# Irrigation_Controller.net
KiCad netlist of a schematic drawn in EAGLE
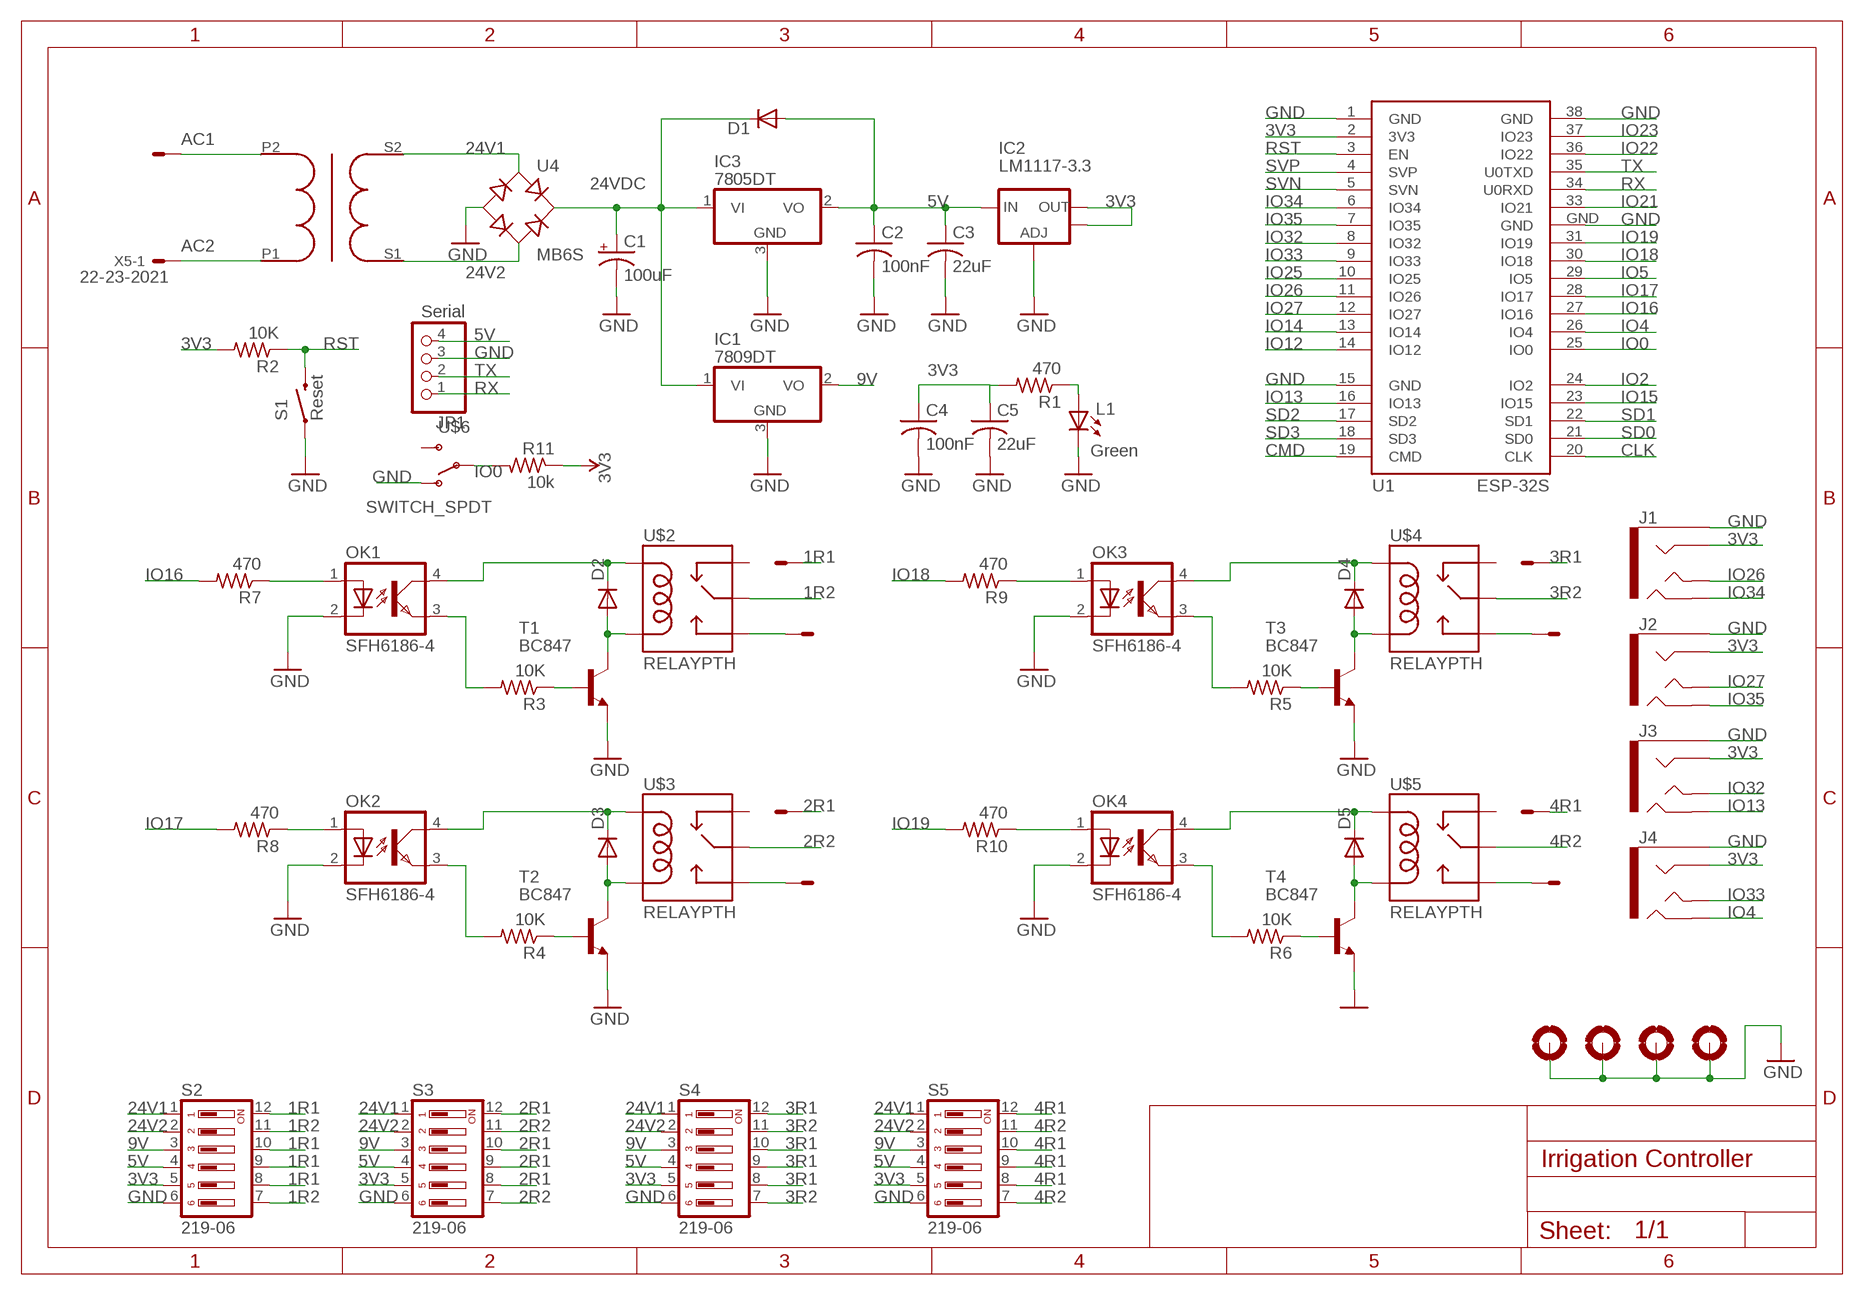
[diagram p0: schematic, sheet 1]

(export (version "E")
  (design (tool "Eeschema 10.0.6"))
  (components
    (comp (ref "C1")
      (value "100uF")
      (footprint "eagle-import:CT7343")
      (libsource (lib "eagle-import") (part "CPOL-USCT7343"))
    )
    (comp (ref "C2")
      (value "100nF")
      (footprint "eagle-import:1206")
      (libsource (lib "eagle-import") (part "C1206"))
    )
    (comp (ref "C3")
      (value "22uF")
      (footprint "eagle-import:1206")
      (libsource (lib "eagle-import") (part "C1206"))
    )
    (comp (ref "C4")
      (value "100nF")
      (footprint "eagle-import:1206")
      (libsource (lib "eagle-import") (part "C1206"))
    )
    (comp (ref "C5")
      (value "22uF")
      (footprint "eagle-import:1206")
      (libsource (lib "eagle-import") (part "C1206"))
    )
    (comp (ref "D1")
      (value "DIODE-SOD123")
      (footprint "eagle-import:SOD123")
      (libsource (lib "eagle-import") (part "DIODE-SOD123"))
    )
    (comp (ref "D2")
      (value "DIODE-SOD123")
      (footprint "eagle-import:SOD123")
      (libsource (lib "eagle-import") (part "DIODE-SOD123"))
    )
    (comp (ref "D3")
      (value "DIODE-SOD123")
      (footprint "eagle-import:SOD123")
      (libsource (lib "eagle-import") (part "DIODE-SOD123"))
    )
    (comp (ref "D4")
      (value "DIODE-SOD123")
      (footprint "eagle-import:SOD123")
      (libsource (lib "eagle-import") (part "DIODE-SOD123"))
    )
    (comp (ref "D5")
      (value "DIODE-SOD123")
      (footprint "eagle-import:SOD123")
      (libsource (lib "eagle-import") (part "DIODE-SOD123"))
    )
    (comp (ref "H1")
      (value "MOUNT-PAD-ROUND3.0")
      (footprint "eagle-import:3,0-PAD")
      (libsource (lib "eagle-import") (part "MOUNT-PAD-ROUND3.0"))
    )
    (comp (ref "H2")
      (value "MOUNT-PAD-ROUND3.0")
      (footprint "eagle-import:3,0-PAD")
      (libsource (lib "eagle-import") (part "MOUNT-PAD-ROUND3.0"))
    )
    (comp (ref "H3")
      (value "MOUNT-PAD-ROUND3.0")
      (footprint "eagle-import:3,0-PAD")
      (libsource (lib "eagle-import") (part "MOUNT-PAD-ROUND3.0"))
    )
    (comp (ref "H4")
      (value "MOUNT-PAD-ROUND3.0")
      (footprint "eagle-import:3,0-PAD")
      (libsource (lib "eagle-import") (part "MOUNT-PAD-ROUND3.0"))
    )
    (comp (ref "IC1")
      (value "7809DT")
      (footprint "eagle-import:TO252")
      (libsource (lib "eagle-import") (part "78DT05"))
    )
    (comp (ref "IC2")
      (value "LM1117-3.3")
      (footprint "eagle-import:SOT223")
      (libsource (lib "eagle-import") (part "V_REG_LM1117SOT223"))
    )
    (comp (ref "IC3")
      (value "7805DT")
      (footprint "eagle-import:TO252")
      (libsource (lib "eagle-import") (part "78DT05"))
    )
    (comp (ref "J1")
      (value "AUDIO_JACK_TRRSSMD_RA")
      (footprint "eagle-import:AUDIO_JACK_3.5MM_TRRS_SMD_RA")
      (libsource (lib "eagle-import") (part "AUDIO_JACK_TRRSSMD_RA"))
    )
    (comp (ref "J2")
      (value "AUDIO_JACK_TRRSSMD_RA")
      (footprint "eagle-import:AUDIO_JACK_3.5MM_TRRS_SMD_RA")
      (libsource (lib "eagle-import") (part "AUDIO_JACK_TRRSSMD_RA"))
    )
    (comp (ref "J3")
      (value "AUDIO_JACK_TRRSSMD_RA")
      (footprint "eagle-import:AUDIO_JACK_3.5MM_TRRS_SMD_RA")
      (libsource (lib "eagle-import") (part "AUDIO_JACK_TRRSSMD_RA"))
    )
    (comp (ref "J4")
      (value "AUDIO_JACK_TRRSSMD_RA")
      (footprint "eagle-import:AUDIO_JACK_3.5MM_TRRS_SMD_RA")
      (libsource (lib "eagle-import") (part "AUDIO_JACK_TRRSSMD_RA"))
    )
    (comp (ref "JP1")
      (value "Serial")
      (footprint "eagle-import:1X04")
      (libsource (lib "eagle-import") (part "PINHD-1X4"))
    )
    (comp (ref "L1")
      (value "Green")
      (footprint "eagle-import:LED1206")
      (libsource (lib "eagle-import") (part "LED1206"))
    )
    (comp (ref "OK1")
      (value "SFH6186-4")
      (footprint "eagle-import:SMD4-7")
      (fields (field (name "MF") "VISHAY/TELEFUNKEN"))
      (libsource (lib "eagle-import") (part "SFH618?6-4"))
    )
    (comp (ref "OK2")
      (value "SFH6186-4")
      (footprint "eagle-import:SMD4-7")
      (fields (field (name "MF") "VISHAY/TELEFUNKEN"))
      (libsource (lib "eagle-import") (part "SFH618?6-4"))
    )
    (comp (ref "OK3")
      (value "SFH6186-4")
      (footprint "eagle-import:SMD4-7")
      (fields (field (name "MF") "VISHAY/TELEFUNKEN"))
      (libsource (lib "eagle-import") (part "SFH618?6-4"))
    )
    (comp (ref "OK4")
      (value "SFH6186-4")
      (footprint "eagle-import:SMD4-7")
      (fields (field (name "MF") "VISHAY/TELEFUNKEN"))
      (libsource (lib "eagle-import") (part "SFH618?6-4"))
    )
    (comp (ref "R1")
      (value "470")
      (footprint "eagle-import:1206")
      (libsource (lib "eagle-import") (part "R1206"))
    )
    (comp (ref "R2")
      (value "10K")
      (footprint "eagle-import:R1206")
      (libsource (lib "eagle-import") (part "R-US_R1206"))
    )
    (comp (ref "R3")
      (value "10K")
      (footprint "eagle-import:R1206")
      (libsource (lib "eagle-import") (part "R-US_R1206"))
    )
    (comp (ref "R4")
      (value "10K")
      (footprint "eagle-import:R1206")
      (libsource (lib "eagle-import") (part "R-US_R1206"))
    )
    (comp (ref "R5")
      (value "10K")
      (footprint "eagle-import:R1206")
      (libsource (lib "eagle-import") (part "R-US_R1206"))
    )
    (comp (ref "R6")
      (value "10K")
      (footprint "eagle-import:R1206")
      (libsource (lib "eagle-import") (part "R-US_R1206"))
    )
    (comp (ref "R7")
      (value "470")
      (footprint "eagle-import:R1206")
      (libsource (lib "eagle-import") (part "R-US_R1206"))
    )
    (comp (ref "R8")
      (value "470")
      (footprint "eagle-import:R1206")
      (libsource (lib "eagle-import") (part "R-US_R1206"))
    )
    (comp (ref "R9")
      (value "470")
      (footprint "eagle-import:R1206")
      (libsource (lib "eagle-import") (part "R-US_R1206"))
    )
    (comp (ref "R10")
      (value "470")
      (footprint "eagle-import:R1206")
      (libsource (lib "eagle-import") (part "R-US_R1206"))
    )
    (comp (ref "R11")
      (value "10k")
      (footprint "eagle-import:1206")
      (libsource (lib "eagle-import") (part "R1206"))
    )
    (comp (ref "S1")
      (value "Reset")
      (footprint "eagle-import:TACTILE_SWITCH_TALL")
      (libsource (lib "eagle-import") (part "SWITCH-MOMENTARY-2SMD-4"))
    )
    (comp (ref "S2")
      (value "219-06")
      (footprint "eagle-import:CTS-219-06")
      (libsource (lib "eagle-import") (part "219-06"))
    )
    (comp (ref "S3")
      (value "219-06")
      (footprint "eagle-import:CTS-219-06")
      (libsource (lib "eagle-import") (part "219-06"))
    )
    (comp (ref "S4")
      (value "219-06")
      (footprint "eagle-import:CTS-219-06")
      (libsource (lib "eagle-import") (part "219-06"))
    )
    (comp (ref "S5")
      (value "219-06")
      (footprint "eagle-import:CTS-219-06")
      (libsource (lib "eagle-import") (part "219-06"))
    )
    (comp (ref "T1")
      (value "BC847")
      (footprint "eagle-import:SOT23")
      (libsource (lib "eagle-import") (part "BC847"))
    )
    (comp (ref "T2")
      (value "BC847")
      (footprint "eagle-import:SOT23")
      (libsource (lib "eagle-import") (part "BC847"))
    )
    (comp (ref "T3")
      (value "BC847")
      (footprint "eagle-import:SOT23")
      (libsource (lib "eagle-import") (part "BC847"))
    )
    (comp (ref "T4")
      (value "BC847")
      (footprint "eagle-import:SOT23")
      (libsource (lib "eagle-import") (part "BC847"))
    )
    (comp (ref "U$1")
      (value "TRANSFORMADOR_PE3010-M")
      (footprint "eagle-import:TRANSFORMADOR_PE3010-M")
      (libsource (lib "eagle-import") (part "TRANSFORMADOR_PE3010-M"))
    )
    (comp (ref "U$2")
      (value "RELAYPTH")
      (footprint "eagle-import:SRD-05VDC-SL-C")
      (libsource (lib "eagle-import") (part "RELAYPTH"))
    )
    (comp (ref "U$3")
      (value "RELAYPTH")
      (footprint "eagle-import:SRD-05VDC-SL-C")
      (libsource (lib "eagle-import") (part "RELAYPTH"))
    )
    (comp (ref "U$4")
      (value "RELAYPTH")
      (footprint "eagle-import:SRD-05VDC-SL-C")
      (libsource (lib "eagle-import") (part "RELAYPTH"))
    )
    (comp (ref "U$5")
      (value "RELAYPTH")
      (footprint "eagle-import:SRD-05VDC-SL-C")
      (libsource (lib "eagle-import") (part "RELAYPTH"))
    )
    (comp (ref "U$6")
      (value "SWITCH_SPDT")
      (footprint "eagle-import:KPS-1290")
      (libsource (lib "eagle-import") (part "SWITCH_SPDT"))
    )
    (comp (ref "U1")
      (value "ESP-32S")
      (footprint "eagle-import:ESP-32S")
      (libsource (lib "eagle-import") (part "ESP-32S"))
    )
    (comp (ref "U4")
      (value "MB6S")
      (footprint "eagle-import:SOIC-4")
      (libsource (lib "eagle-import") (part "MBS6"))
    )
    (comp (ref "X1")
      (value "22-23-2021")
      (footprint "eagle-import:22-23-2021")
      (fields (field (name "MF") "MOLEX"))
      (libsource (lib "eagle-import") (part "22-23-2021"))
    )
    (comp (ref "X2")
      (value "22-23-2021")
      (footprint "eagle-import:22-23-2021")
      (fields (field (name "MF") "MOLEX"))
      (libsource (lib "eagle-import") (part "22-23-2021"))
    )
    (comp (ref "X3")
      (value "22-23-2021")
      (footprint "eagle-import:22-23-2021")
      (fields (field (name "MF") "MOLEX"))
      (libsource (lib "eagle-import") (part "22-23-2021"))
    )
    (comp (ref "X4")
      (value "22-23-2021")
      (footprint "eagle-import:22-23-2021")
      (fields (field (name "MF") "MOLEX"))
      (libsource (lib "eagle-import") (part "22-23-2021"))
    )
    (comp (ref "X5")
      (value "22-23-2021")
      (footprint "eagle-import:22-23-2021")
      (fields (field (name "MF") "MOLEX"))
      (libsource (lib "eagle-import") (part "22-23-2021"))
    )
  )
  (nets
    (net (code "1") (name "/1R1") (class "Default")
      (node (ref "S2") (pin "10") (pinfunction "10_10") (pintype "passive"))
      (node (ref "S2") (pin "12") (pinfunction "12_12") (pintype "passive"))
      (node (ref "S2") (pin "8") (pinfunction "8_8") (pintype "passive"))
      (node (ref "S2") (pin "9") (pinfunction "9_9") (pintype "passive"))
      (node (ref "X1") (pin "1") (pinfunction "S_1") (pintype "passive"))
    )
    (net (code "2") (name "/1R2") (class "Default")
      (node (ref "S2") (pin "11") (pinfunction "11_11") (pintype "passive"))
      (node (ref "S2") (pin "7") (pinfunction "7_7") (pintype "passive"))
      (node (ref "U$2") (pin "SWCOMMON") (pinfunction "SWCOMMON_SWCOMMON") (pintype "bidirectional"))
    )
    (net (code "3") (name "/2R1") (class "Default")
      (node (ref "S3") (pin "10") (pinfunction "10_10") (pintype "passive"))
      (node (ref "S3") (pin "12") (pinfunction "12_12") (pintype "passive"))
      (node (ref "S3") (pin "8") (pinfunction "8_8") (pintype "passive"))
      (node (ref "S3") (pin "9") (pinfunction "9_9") (pintype "passive"))
      (node (ref "X2") (pin "1") (pinfunction "S_1") (pintype "passive"))
    )
    (net (code "4") (name "/2R2") (class "Default")
      (node (ref "S3") (pin "11") (pinfunction "11_11") (pintype "passive"))
      (node (ref "S3") (pin "7") (pinfunction "7_7") (pintype "passive"))
      (node (ref "U$3") (pin "SWCOMMON") (pinfunction "SWCOMMON_SWCOMMON") (pintype "bidirectional"))
    )
    (net (code "5") (name "/3R1") (class "Default")
      (node (ref "S4") (pin "10") (pinfunction "10_10") (pintype "passive"))
      (node (ref "S4") (pin "12") (pinfunction "12_12") (pintype "passive"))
      (node (ref "S4") (pin "8") (pinfunction "8_8") (pintype "passive"))
      (node (ref "S4") (pin "9") (pinfunction "9_9") (pintype "passive"))
      (node (ref "X3") (pin "1") (pinfunction "S_1") (pintype "passive"))
    )
    (net (code "6") (name "/3R2") (class "Default")
      (node (ref "S4") (pin "11") (pinfunction "11_11") (pintype "passive"))
      (node (ref "S4") (pin "7") (pinfunction "7_7") (pintype "passive"))
      (node (ref "U$4") (pin "SWCOMMON") (pinfunction "SWCOMMON_SWCOMMON") (pintype "bidirectional"))
    )
    (net (code "7") (name "/4R1") (class "Default")
      (node (ref "S5") (pin "10") (pinfunction "10_10") (pintype "passive"))
      (node (ref "S5") (pin "12") (pinfunction "12_12") (pintype "passive"))
      (node (ref "S5") (pin "8") (pinfunction "8_8") (pintype "passive"))
      (node (ref "S5") (pin "9") (pinfunction "9_9") (pintype "passive"))
      (node (ref "X4") (pin "1") (pinfunction "S_1") (pintype "passive"))
    )
    (net (code "8") (name "/4R2") (class "Default")
      (node (ref "S5") (pin "11") (pinfunction "11_11") (pintype "passive"))
      (node (ref "S5") (pin "7") (pinfunction "7_7") (pintype "passive"))
      (node (ref "U$5") (pin "SWCOMMON") (pinfunction "SWCOMMON_SWCOMMON") (pintype "bidirectional"))
    )
    (net (code "9") (name "/5V") (class "Default")
      (node (ref "C2") (pin "1") (pinfunction "1_1") (pintype "passive"))
      (node (ref "C3") (pin "1") (pinfunction "1_1") (pintype "passive"))
      (node (ref "D1") (pin "A") (pinfunction "A_A") (pintype "passive"))
      (node (ref "IC2") (pin "3") (pinfunction "IN_3") (pintype "input"))
      (node (ref "IC3") (pin "2") (pinfunction "VO_2") (pintype "passive"))
      (node (ref "JP1") (pin "4") (pinfunction "4_4") (pintype "passive"))
      (node (ref "S2") (pin "4") (pinfunction "4_4") (pintype "passive"))
      (node (ref "S3") (pin "4") (pinfunction "4_4") (pintype "passive"))
      (node (ref "S4") (pin "4") (pinfunction "4_4") (pintype "passive"))
      (node (ref "S5") (pin "4") (pinfunction "4_4") (pintype "passive"))
    )
    (net (code "10") (name "/9V") (class "Default")
      (node (ref "IC1") (pin "2") (pinfunction "VO_2") (pintype "passive"))
      (node (ref "S2") (pin "3") (pinfunction "3_3") (pintype "passive"))
      (node (ref "S3") (pin "3") (pinfunction "3_3") (pintype "passive"))
      (node (ref "S4") (pin "3") (pinfunction "3_3") (pintype "passive"))
      (node (ref "S5") (pin "3") (pinfunction "3_3") (pintype "passive"))
    )
    (net (code "11") (name "/24V1") (class "Default")
      (node (ref "S2") (pin "1") (pinfunction "1_1") (pintype "passive"))
      (node (ref "S3") (pin "1") (pinfunction "1_1") (pintype "passive"))
      (node (ref "S4") (pin "1") (pinfunction "1_1") (pintype "passive"))
      (node (ref "S5") (pin "1") (pinfunction "1_1") (pintype "passive"))
      (node (ref "U$1") (pin "S2") (pinfunction "S2_S2") (pintype "bidirectional"))
      (node (ref "U4") (pin "~1") (pinfunction "AC1_~1") (pintype "passive"))
    )
    (net (code "12") (name "/24V2") (class "Default")
      (node (ref "S2") (pin "2") (pinfunction "2_2") (pintype "passive"))
      (node (ref "S3") (pin "2") (pinfunction "2_2") (pintype "passive"))
      (node (ref "S4") (pin "2") (pinfunction "2_2") (pintype "passive"))
      (node (ref "S5") (pin "2") (pinfunction "2_2") (pintype "passive"))
      (node (ref "U$1") (pin "S1") (pinfunction "S1_S1") (pintype "bidirectional"))
      (node (ref "U4") (pin "~2") (pinfunction "AC2_~2") (pintype "passive"))
    )
    (net (code "13") (name "/24VDC") (class "Default")
      (node (ref "C1") (pin "+") (pinfunction "+_+") (pintype "passive"))
      (node (ref "D1") (pin "C") (pinfunction "C_C") (pintype "passive"))
      (node (ref "IC1") (pin "1") (pinfunction "VI_1") (pintype "input"))
      (node (ref "IC3") (pin "1") (pinfunction "VI_1") (pintype "input"))
      (node (ref "U4") (pin "+") (pinfunction "+_+") (pintype "passive"))
    )
    (net (code "14") (name "/AC1") (class "Default")
      (node (ref "U$1") (pin "P2") (pinfunction "P2_P2") (pintype "bidirectional"))
      (node (ref "X5") (pin "2") (pinfunction "S_2") (pintype "passive"))
    )
    (net (code "15") (name "/AC2") (class "Default")
      (node (ref "U$1") (pin "P1") (pinfunction "P1_P1") (pintype "bidirectional"))
      (node (ref "X5") (pin "1") (pinfunction "S_1") (pintype "passive"))
    )
    (net (code "16") (name "/CLK") (class "Default")
      (node (ref "U1") (pin "20") (pinfunction "CLK_20") (pintype "bidirectional"))
    )
    (net (code "17") (name "/CMD") (class "Default")
      (node (ref "U1") (pin "19") (pinfunction "CMD_19") (pintype "bidirectional"))
    )
    (net (code "18") (name "/IO0") (class "Default")
      (node (ref "R11") (pin "2") (pinfunction "2_2") (pintype "passive"))
      (node (ref "U$6") (pin "P") (pinfunction "P_P") (pintype "passive"))
      (node (ref "U1") (pin "25") (pinfunction "IO0_25") (pintype "bidirectional"))
    )
    (net (code "19") (name "/IO2") (class "Default")
      (node (ref "U1") (pin "24") (pinfunction "IO2_24") (pintype "bidirectional"))
    )
    (net (code "20") (name "/IO4") (class "Default")
      (node (ref "J4") (pin "RING2") (pinfunction "RING2_RING2") (pintype "bidirectional"))
      (node (ref "U1") (pin "26") (pinfunction "IO4_26") (pintype "bidirectional"))
    )
    (net (code "21") (name "/IO5") (class "Default")
      (node (ref "U1") (pin "29") (pinfunction "IO5_29") (pintype "bidirectional"))
    )
    (net (code "22") (name "/IO12") (class "Default")
      (node (ref "U1") (pin "14") (pinfunction "IO12_14") (pintype "bidirectional"))
    )
    (net (code "23") (name "/IO13") (class "Default")
      (node (ref "J3") (pin "RING2") (pinfunction "RING2_RING2") (pintype "bidirectional"))
      (node (ref "U1") (pin "16") (pinfunction "IO13_16") (pintype "bidirectional"))
    )
    (net (code "24") (name "/IO14") (class "Default")
      (node (ref "U1") (pin "13") (pinfunction "IO14_13") (pintype "bidirectional"))
    )
    (net (code "25") (name "/IO15") (class "Default")
      (node (ref "U1") (pin "23") (pinfunction "IO15_23") (pintype "bidirectional"))
    )
    (net (code "26") (name "/IO16") (class "Default")
      (node (ref "R7") (pin "2") (pinfunction "2_2") (pintype "passive"))
      (node (ref "U1") (pin "27") (pinfunction "IO16_27") (pintype "bidirectional"))
    )
    (net (code "27") (name "/IO17") (class "Default")
      (node (ref "R8") (pin "2") (pinfunction "2_2") (pintype "passive"))
      (node (ref "U1") (pin "28") (pinfunction "IO17_28") (pintype "bidirectional"))
    )
    (net (code "28") (name "/IO18") (class "Default")
      (node (ref "R9") (pin "2") (pinfunction "2_2") (pintype "passive"))
      (node (ref "U1") (pin "30") (pinfunction "IO18_30") (pintype "bidirectional"))
    )
    (net (code "29") (name "/IO19") (class "Default")
      (node (ref "R10") (pin "2") (pinfunction "2_2") (pintype "passive"))
      (node (ref "U1") (pin "31") (pinfunction "IO19_31") (pintype "bidirectional"))
    )
    (net (code "30") (name "/IO21") (class "Default")
      (node (ref "U1") (pin "33") (pinfunction "IO21_33") (pintype "bidirectional"))
    )
    (net (code "31") (name "/IO22") (class "Default")
      (node (ref "U1") (pin "36") (pinfunction "IO22_36") (pintype "bidirectional"))
    )
    (net (code "32") (name "/IO23") (class "Default")
      (node (ref "U1") (pin "37") (pinfunction "IO23_37") (pintype "bidirectional"))
    )
    (net (code "33") (name "/IO25") (class "Default")
      (node (ref "U1") (pin "10") (pinfunction "IO25_10") (pintype "bidirectional"))
    )
    (net (code "34") (name "/IO26") (class "Default")
      (node (ref "J1") (pin "TIP") (pinfunction "TIP_TIP") (pintype "bidirectional"))
      (node (ref "U1") (pin "11") (pinfunction "IO26_11") (pintype "bidirectional"))
    )
    (net (code "35") (name "/IO27") (class "Default")
      (node (ref "J2") (pin "TIP") (pinfunction "TIP_TIP") (pintype "bidirectional"))
      (node (ref "U1") (pin "12") (pinfunction "IO27_12") (pintype "bidirectional"))
    )
    (net (code "36") (name "/IO32") (class "Default")
      (node (ref "J3") (pin "TIP") (pinfunction "TIP_TIP") (pintype "bidirectional"))
      (node (ref "U1") (pin "8") (pinfunction "IO32_8") (pintype "bidirectional"))
    )
    (net (code "37") (name "/IO33") (class "Default")
      (node (ref "J4") (pin "TIP") (pinfunction "TIP_TIP") (pintype "bidirectional"))
      (node (ref "U1") (pin "9") (pinfunction "IO33_9") (pintype "bidirectional"))
    )
    (net (code "38") (name "/IO34") (class "Default")
      (node (ref "J1") (pin "RING2") (pinfunction "RING2_RING2") (pintype "bidirectional"))
      (node (ref "U1") (pin "6") (pinfunction "IO34_6") (pintype "bidirectional"))
    )
    (net (code "39") (name "/IO35") (class "Default")
      (node (ref "J2") (pin "RING2") (pinfunction "RING2_RING2") (pintype "bidirectional"))
      (node (ref "U1") (pin "7") (pinfunction "IO35_7") (pintype "bidirectional"))
    )
    (net (code "40") (name "/RST") (class "Default")
      (node (ref "R2") (pin "1") (pinfunction "1_1") (pintype "passive"))
      (node (ref "S1") (pin "B2") (pinfunction "2_B2") (pintype "passive"))
      (node (ref "U1") (pin "3") (pinfunction "EN_3") (pintype "input"))
    )
    (net (code "41") (name "/RX") (class "Default")
      (node (ref "JP1") (pin "1") (pinfunction "1_1") (pintype "passive"))
      (node (ref "U1") (pin "34") (pinfunction "U0RXD_34") (pintype "bidirectional"))
    )
    (net (code "42") (name "/SD0") (class "Default")
      (node (ref "U1") (pin "21") (pinfunction "SD0_21") (pintype "bidirectional"))
    )
    (net (code "43") (name "/SD1") (class "Default")
      (node (ref "U1") (pin "22") (pinfunction "SD1_22") (pintype "bidirectional"))
    )
    (net (code "44") (name "/SD2") (class "Default")
      (node (ref "U1") (pin "17") (pinfunction "SD2_17") (pintype "bidirectional"))
    )
    (net (code "45") (name "/SD3") (class "Default")
      (node (ref "U1") (pin "18") (pinfunction "SD3_18") (pintype "bidirectional"))
    )
    (net (code "46") (name "/SVN") (class "Default")
      (node (ref "U1") (pin "5") (pinfunction "SVN_5") (pintype "bidirectional"))
    )
    (net (code "47") (name "/SVP") (class "Default")
      (node (ref "U1") (pin "4") (pinfunction "SVP_4") (pintype "bidirectional"))
    )
    (net (code "48") (name "/TX") (class "Default")
      (node (ref "JP1") (pin "2") (pinfunction "2_2") (pintype "passive"))
      (node (ref "U1") (pin "35") (pinfunction "U0TXD_35") (pintype "bidirectional"))
    )
    (net (code "49") (name "GND") (class "Default")
      (node (ref "C1") (pin "-") (pinfunction "-_-") (pintype "passive"))
      (node (ref "C2") (pin "2") (pinfunction "2_2") (pintype "passive"))
      (node (ref "C3") (pin "2") (pinfunction "2_2") (pintype "passive"))
      (node (ref "C4") (pin "2") (pinfunction "2_2") (pintype "passive"))
      (node (ref "C5") (pin "2") (pinfunction "2_2") (pintype "passive"))
      (node (ref "H1") (pin "B3,0") (pinfunction "MOUNT_B3,0") (pintype "passive"))
      (node (ref "H2") (pin "B3,0") (pinfunction "MOUNT_B3,0") (pintype "passive"))
      (node (ref "H3") (pin "B3,0") (pinfunction "MOUNT_B3,0") (pintype "passive"))
      (node (ref "H4") (pin "B3,0") (pinfunction "MOUNT_B3,0") (pintype "passive"))
      (node (ref "IC1") (pin "3") (pinfunction "GND_3") (pintype "passive"))
      (node (ref "IC2") (pin "1") (pinfunction "ADJ_1") (pintype "input"))
      (node (ref "IC3") (pin "3") (pinfunction "GND_3") (pintype "passive"))
      (node (ref "J1") (pin "EARTH") (pinfunction "EARTH_EARTH") (pintype "bidirectional"))
      (node (ref "J2") (pin "EARTH") (pinfunction "EARTH_EARTH") (pintype "bidirectional"))
      (node (ref "J3") (pin "EARTH") (pinfunction "EARTH_EARTH") (pintype "bidirectional"))
      (node (ref "J4") (pin "EARTH") (pinfunction "EARTH_EARTH") (pintype "bidirectional"))
      (node (ref "JP1") (pin "3") (pinfunction "3_3") (pintype "passive"))
      (node (ref "L1") (pin "C") (pinfunction "C_C") (pintype "passive"))
      (node (ref "OK1") (pin "2") (pinfunction "C_2") (pintype "passive"))
      (node (ref "OK2") (pin "2") (pinfunction "C_2") (pintype "passive"))
      (node (ref "OK3") (pin "2") (pinfunction "C_2") (pintype "passive"))
      (node (ref "OK4") (pin "2") (pinfunction "C_2") (pintype "passive"))
      (node (ref "S1") (pin "A2") (pinfunction "1_A2") (pintype "passive"))
      (node (ref "S2") (pin "6") (pinfunction "6_6") (pintype "passive"))
      (node (ref "S3") (pin "6") (pinfunction "6_6") (pintype "passive"))
      (node (ref "S4") (pin "6") (pinfunction "6_6") (pintype "passive"))
      (node (ref "S5") (pin "6") (pinfunction "6_6") (pintype "passive"))
      (node (ref "T1") (pin "2") (pinfunction "E_2") (pintype "passive"))
      (node (ref "T2") (pin "2") (pinfunction "E_2") (pintype "passive"))
      (node (ref "T3") (pin "2") (pinfunction "E_2") (pintype "passive"))
      (node (ref "T4") (pin "2") (pinfunction "E_2") (pintype "passive"))
      (node (ref "U$6") (pin "O") (pinfunction "O_O") (pintype "passive"))
      (node (ref "U1") (pin "1") (pinfunction "GND_1") (pintype "power_in"))
      (node (ref "U1") (pin "15") (pinfunction "GND_15") (pintype "power_in"))
      (node (ref "U1") (pin "38") (pinfunction "GND_38") (pintype "power_in"))
      (node (ref "U1") (pin "GND") (pinfunction "GND_GND") (pintype "power_in"))
      (node (ref "U4") (pin "-") (pinfunction "-_-") (pintype "passive"))
    )
    (net (code "50") (name "Net-(L1-PadA)") (class "Default")
      (node (ref "L1") (pin "A") (pinfunction "A_A") (pintype "passive"))
      (node (ref "R1") (pin "1") (pinfunction "1_1") (pintype "passive"))
    )
    (net (code "51") (name "Net-(OK1-A)") (class "Default")
      (node (ref "OK1") (pin "1") (pinfunction "A_1") (pintype "passive"))
      (node (ref "R7") (pin "1") (pinfunction "1_1") (pintype "passive"))
    )
    (net (code "52") (name "Net-(OK1-COL)") (class "Default")
      (node (ref "D2") (pin "C") (pinfunction "C_C") (pintype "passive"))
      (node (ref "OK1") (pin "4") (pinfunction "COL_4") (pintype "passive"))
      (node (ref "U$2") (pin "COIL1") (pinfunction "COIL1_COIL1") (pintype "bidirectional"))
    )
    (net (code "53") (name "Net-(OK1-EMIT)") (class "Default")
      (node (ref "OK1") (pin "3") (pinfunction "EMIT_3") (pintype "passive"))
      (node (ref "R3") (pin "2") (pinfunction "2_2") (pintype "passive"))
    )
    (net (code "54") (name "Net-(OK2-A)") (class "Default")
      (node (ref "OK2") (pin "1") (pinfunction "A_1") (pintype "passive"))
      (node (ref "R8") (pin "1") (pinfunction "1_1") (pintype "passive"))
    )
    (net (code "55") (name "Net-(OK2-COL)") (class "Default")
      (node (ref "D3") (pin "C") (pinfunction "C_C") (pintype "passive"))
      (node (ref "OK2") (pin "4") (pinfunction "COL_4") (pintype "passive"))
      (node (ref "U$3") (pin "COIL1") (pinfunction "COIL1_COIL1") (pintype "bidirectional"))
    )
    (net (code "56") (name "Net-(OK2-EMIT)") (class "Default")
      (node (ref "OK2") (pin "3") (pinfunction "EMIT_3") (pintype "passive"))
      (node (ref "R4") (pin "2") (pinfunction "2_2") (pintype "passive"))
    )
    (net (code "57") (name "Net-(OK3-A)") (class "Default")
      (node (ref "OK3") (pin "1") (pinfunction "A_1") (pintype "passive"))
      (node (ref "R9") (pin "1") (pinfunction "1_1") (pintype "passive"))
    )
    (net (code "58") (name "Net-(OK3-COL)") (class "Default")
      (node (ref "D4") (pin "C") (pinfunction "C_C") (pintype "passive"))
      (node (ref "OK3") (pin "4") (pinfunction "COL_4") (pintype "passive"))
      (node (ref "U$4") (pin "COIL1") (pinfunction "COIL1_COIL1") (pintype "bidirectional"))
    )
    (net (code "59") (name "Net-(OK3-EMIT)") (class "Default")
      (node (ref "OK3") (pin "3") (pinfunction "EMIT_3") (pintype "passive"))
      (node (ref "R5") (pin "2") (pinfunction "2_2") (pintype "passive"))
    )
    (net (code "60") (name "Net-(OK4-A)") (class "Default")
      (node (ref "OK4") (pin "1") (pinfunction "A_1") (pintype "passive"))
      (node (ref "R10") (pin "1") (pinfunction "1_1") (pintype "passive"))
    )
    (net (code "61") (name "Net-(OK4-COL)") (class "Default")
      (node (ref "D5") (pin "C") (pinfunction "C_C") (pintype "passive"))
      (node (ref "OK4") (pin "4") (pinfunction "COL_4") (pintype "passive"))
      (node (ref "U$5") (pin "COIL1") (pinfunction "COIL1_COIL1") (pintype "bidirectional"))
    )
    (net (code "62") (name "Net-(OK4-EMIT)") (class "Default")
      (node (ref "OK4") (pin "3") (pinfunction "EMIT_3") (pintype "passive"))
      (node (ref "R6") (pin "2") (pinfunction "2_2") (pintype "passive"))
    )
    (net (code "63") (name "Net-(T1-B)") (class "Default")
      (node (ref "R3") (pin "1") (pinfunction "1_1") (pintype "passive"))
      (node (ref "T1") (pin "1") (pinfunction "B_1") (pintype "passive"))
    )
    (net (code "64") (name "Net-(T1-C)") (class "Default")
      (node (ref "D2") (pin "A") (pinfunction "A_A") (pintype "passive"))
      (node (ref "T1") (pin "3") (pinfunction "C_3") (pintype "passive"))
      (node (ref "U$2") (pin "COIL0") (pinfunction "COIL0_COIL0") (pintype "bidirectional"))
    )
    (net (code "65") (name "Net-(T2-B)") (class "Default")
      (node (ref "R4") (pin "1") (pinfunction "1_1") (pintype "passive"))
      (node (ref "T2") (pin "1") (pinfunction "B_1") (pintype "passive"))
    )
    (net (code "66") (name "Net-(T2-C)") (class "Default")
      (node (ref "D3") (pin "A") (pinfunction "A_A") (pintype "passive"))
      (node (ref "T2") (pin "3") (pinfunction "C_3") (pintype "passive"))
      (node (ref "U$3") (pin "COIL0") (pinfunction "COIL0_COIL0") (pintype "bidirectional"))
    )
    (net (code "67") (name "Net-(T3-B)") (class "Default")
      (node (ref "R5") (pin "1") (pinfunction "1_1") (pintype "passive"))
      (node (ref "T3") (pin "1") (pinfunction "B_1") (pintype "passive"))
    )
    (net (code "68") (name "Net-(T3-C)") (class "Default")
      (node (ref "D4") (pin "A") (pinfunction "A_A") (pintype "passive"))
      (node (ref "T3") (pin "3") (pinfunction "C_3") (pintype "passive"))
      (node (ref "U$4") (pin "COIL0") (pinfunction "COIL0_COIL0") (pintype "bidirectional"))
    )
    (net (code "69") (name "Net-(T4-B)") (class "Default")
      (node (ref "R6") (pin "1") (pinfunction "1_1") (pintype "passive"))
      (node (ref "T4") (pin "1") (pinfunction "B_1") (pintype "passive"))
    )
    (net (code "70") (name "Net-(T4-C)") (class "Default")
      (node (ref "D5") (pin "A") (pinfunction "A_A") (pintype "passive"))
      (node (ref "T4") (pin "3") (pinfunction "C_3") (pintype "passive"))
      (node (ref "U$5") (pin "COIL0") (pinfunction "COIL0_COIL0") (pintype "bidirectional"))
    )
    (net (code "71") (name "Net-(X1B-S)") (class "Default")
      (node (ref "U$2") (pin "SWOPEN") (pinfunction "SWOPEN_SWOPEN") (pintype "bidirectional"))
      (node (ref "X1") (pin "2") (pinfunction "S_2") (pintype "passive"))
    )
    (net (code "72") (name "Net-(X2B-S)") (class "Default")
      (node (ref "U$3") (pin "SWOPEN") (pinfunction "SWOPEN_SWOPEN") (pintype "bidirectional"))
      (node (ref "X2") (pin "2") (pinfunction "S_2") (pintype "passive"))
    )
    (net (code "73") (name "Net-(X3B-S)") (class "Default")
      (node (ref "U$4") (pin "SWOPEN") (pinfunction "SWOPEN_SWOPEN") (pintype "bidirectional"))
      (node (ref "X3") (pin "2") (pinfunction "S_2") (pintype "passive"))
    )
    (net (code "74") (name "Net-(X4B-S)") (class "Default")
      (node (ref "U$5") (pin "SWOPEN") (pinfunction "SWOPEN_SWOPEN") (pintype "bidirectional"))
      (node (ref "X4") (pin "2") (pinfunction "S_2") (pintype "passive"))
    )
    (net (code "75") (name "VCC") (class "Default")
      (node (ref "C4") (pin "1") (pinfunction "1_1") (pintype "passive"))
      (node (ref "C5") (pin "1") (pinfunction "1_1") (pintype "passive"))
      (node (ref "IC2") (pin "2") (pinfunction "OUT_2") (pintype "output"))
      (node (ref "IC2") (pin "4") (pinfunction "OUT_4") (pintype "output"))
      (node (ref "J1") (pin "RING1") (pinfunction "RING1_RING1") (pintype "bidirectional"))
      (node (ref "J2") (pin "RING1") (pinfunction "RING1_RING1") (pintype "bidirectional"))
      (node (ref "J3") (pin "RING1") (pinfunction "RING1_RING1") (pintype "bidirectional"))
      (node (ref "J4") (pin "RING1") (pinfunction "RING1_RING1") (pintype "bidirectional"))
      (node (ref "R1") (pin "2") (pinfunction "2_2") (pintype "passive"))
      (node (ref "R11") (pin "1") (pinfunction "1_1") (pintype "passive"))
      (node (ref "R2") (pin "2") (pinfunction "2_2") (pintype "passive"))
      (node (ref "S2") (pin "5") (pinfunction "5_5") (pintype "passive"))
      (node (ref "S3") (pin "5") (pinfunction "5_5") (pintype "passive"))
      (node (ref "S4") (pin "5") (pinfunction "5_5") (pintype "passive"))
      (node (ref "S5") (pin "5") (pinfunction "5_5") (pintype "passive"))
      (node (ref "U1") (pin "2") (pinfunction "3V3_2") (pintype "power_in"))
    )
    (net (code "76") (name "unconnected-(U$2-SWCLOSE-PadSWCLOSED)") (class "Default")
      (node (ref "U$2") (pin "SWCLOSED") (pinfunction "SWCLOSE_SWCLOSED") (pintype "bidirectional"))
    )
    (net (code "77") (name "unconnected-(U$3-SWCLOSE-PadSWCLOSED)") (class "Default")
      (node (ref "U$3") (pin "SWCLOSED") (pinfunction "SWCLOSE_SWCLOSED") (pintype "bidirectional"))
    )
    (net (code "78") (name "unconnected-(U$4-SWCLOSE-PadSWCLOSED)") (class "Default")
      (node (ref "U$4") (pin "SWCLOSED") (pinfunction "SWCLOSE_SWCLOSED") (pintype "bidirectional"))
    )
    (net (code "79") (name "unconnected-(U$5-SWCLOSE-PadSWCLOSED)") (class "Default")
      (node (ref "U$5") (pin "SWCLOSED") (pinfunction "SWCLOSE_SWCLOSED") (pintype "bidirectional"))
    )
    (net (code "80") (name "unconnected-(U$6-PadS)") (class "Default")
      (node (ref "U$6") (pin "S") (pinfunction "S_S") (pintype "passive"))
    )
  )
)
